# atmega32u4-tqfp44-breakout.net
KiCad netlist of a schematic drawn in EAGLE
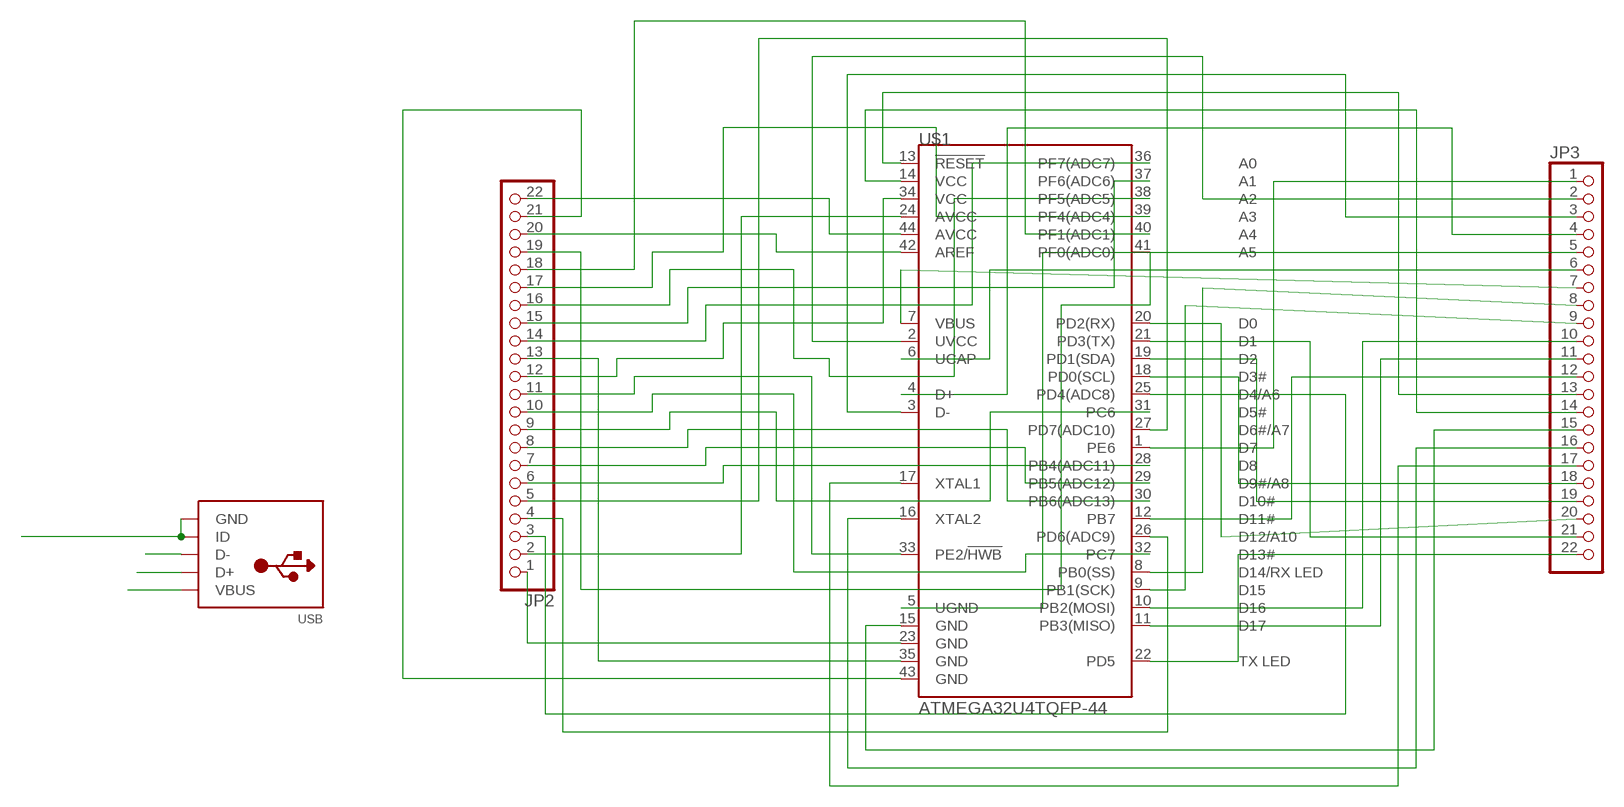
[diagram p0: schematic, sheet 1]

(export (version "E")
  (design (tool "Eeschema 10.0.6"))
  (components
    (comp (ref "JP2")
      (value "PINHD-1X22")
      (footprint "eagle-import:1X22")
      (libsource (lib "eagle-import") (part "PINHD-1X22"))
    )
    (comp (ref "JP3")
      (value "PINHD-1X22")
      (footprint "eagle-import:1X22")
      (libsource (lib "eagle-import") (part "PINHD-1X22"))
    )
    (comp (ref "U$1")
      (value "ATMEGA32U4TQFP-44")
      (footprint "eagle-import:TQFP44")
      (libsource (lib "eagle-import") (part "ATMEGA32U4TQFP-44"))
    )
    (comp (ref "USB")
      (value "USBMOLEX")
      (footprint "eagle-import:USB-MINIB-THM-MOLEX")
      (libsource (lib "eagle-import") (part "USBMOLEX"))
    )
  )
  (nets
    (net (code "1") (name "/N$21") (class "Default")
      (node (ref "JP3") (pin "22") (pinfunction "22_22") (pintype "passive"))
      (node (ref "U$1") (pin "22") (pinfunction "PD5_22") (pintype "bidirectional"))
      (node (ref "USB") (pin "D-") (pinfunction "D-_D-") (pintype "bidirectional"))
    )
    (net (code "2") (name "/N$23") (class "Default")
      (node (ref "JP2") (pin "1") (pinfunction "1_1") (pintype "passive"))
      (node (ref "U$1") (pin "23") (pinfunction "GND_23") (pintype "bidirectional"))
      (node (ref "USB") (pin "D+") (pinfunction "D+_D+") (pintype "bidirectional"))
    )
    (net (code "3") (name "Net-(JP2-Pad2)") (class "Default")
      (node (ref "JP2") (pin "2") (pinfunction "2_2") (pintype "passive"))
      (node (ref "U$1") (pin "24") (pinfunction "AVCC_24") (pintype "bidirectional"))
    )
    (net (code "4") (name "Net-(JP2-Pad12)") (class "Default")
      (node (ref "JP2") (pin "12") (pinfunction "12_12") (pintype "passive"))
      (node (ref "U$1") (pin "34") (pinfunction "VCC_34") (pintype "bidirectional"))
    )
    (net (code "5") (name "Net-(JP2-Pad13)") (class "Default")
      (node (ref "JP2") (pin "13") (pinfunction "13_13") (pintype "passive"))
      (node (ref "U$1") (pin "35") (pinfunction "GND_35") (pintype "bidirectional"))
    )
    (net (code "6") (name "Net-(JP2-Pad21)") (class "Default")
      (node (ref "JP2") (pin "21") (pinfunction "21_21") (pintype "passive"))
      (node (ref "U$1") (pin "43") (pinfunction "GND_43") (pintype "bidirectional"))
    )
    (net (code "7") (name "Net-(JP2-Pad22)") (class "Default")
      (node (ref "JP2") (pin "22") (pinfunction "22_22") (pintype "passive"))
      (node (ref "U$1") (pin "44") (pinfunction "AVCC_44") (pintype "bidirectional"))
    )
    (net (code "8") (name "Net-(JP3-Pad14)") (class "Default")
      (node (ref "JP3") (pin "14") (pinfunction "14_14") (pintype "passive"))
      (node (ref "U$1") (pin "14") (pinfunction "VCC_14") (pintype "bidirectional"))
    )
    (net (code "9") (name "Net-(JP3-Pad15)") (class "Default")
      (node (ref "JP3") (pin "15") (pinfunction "15_15") (pintype "passive"))
      (node (ref "U$1") (pin "15") (pinfunction "GND_15") (pintype "bidirectional"))
    )
    (net (code "10") (name "Net-(U$1-AREF)") (class "Default")
      (node (ref "JP2") (pin "20") (pinfunction "20_20") (pintype "passive"))
      (node (ref "U$1") (pin "42") (pinfunction "AREF_42") (pintype "bidirectional"))
    )
    (net (code "11") (name "Net-(U$1-D+)") (class "Default")
      (node (ref "JP3") (pin "4") (pinfunction "4_4") (pintype "passive"))
      (node (ref "U$1") (pin "4") (pinfunction "D+_4") (pintype "bidirectional"))
    )
    (net (code "12") (name "Net-(U$1-D-)") (class "Default")
      (node (ref "JP3") (pin "3") (pinfunction "3_3") (pintype "passive"))
      (node (ref "U$1") (pin "3") (pinfunction "D-_3") (pintype "bidirectional"))
    )
    (net (code "13") (name "Net-(U$1-PB0(SS))") (class "Default")
      (node (ref "JP3") (pin "8") (pinfunction "8_8") (pintype "passive"))
      (node (ref "U$1") (pin "8") (pinfunction "PB0(SS)_8") (pintype "bidirectional"))
    )
    (net (code "14") (name "Net-(U$1-PB1(SCK))") (class "Default")
      (node (ref "JP3") (pin "9") (pinfunction "9_9") (pintype "passive"))
      (node (ref "U$1") (pin "9") (pinfunction "PB1(SCK)_9") (pintype "bidirectional"))
    )
    (net (code "15") (name "Net-(U$1-PB2(MOSI))") (class "Default")
      (node (ref "JP3") (pin "10") (pinfunction "10_10") (pintype "passive"))
      (node (ref "U$1") (pin "10") (pinfunction "PB2(MOSI)_10") (pintype "bidirectional"))
    )
    (net (code "16") (name "Net-(U$1-PB3(MISO))") (class "Default")
      (node (ref "JP3") (pin "11") (pinfunction "11_11") (pintype "passive"))
      (node (ref "U$1") (pin "11") (pinfunction "PB3(MISO)_11") (pintype "bidirectional"))
    )
    (net (code "17") (name "Net-(U$1-PB4(ADC11))") (class "Default")
      (node (ref "JP2") (pin "6") (pinfunction "6_6") (pintype "passive"))
      (node (ref "U$1") (pin "28") (pinfunction "PB4(ADC11)_28") (pintype "bidirectional"))
    )
    (net (code "18") (name "Net-(U$1-PB5(ADC12))") (class "Default")
      (node (ref "JP2") (pin "7") (pinfunction "7_7") (pintype "passive"))
      (node (ref "U$1") (pin "29") (pinfunction "PB5(ADC12)_29") (pintype "bidirectional"))
    )
    (net (code "19") (name "Net-(U$1-PB6(ADC13))") (class "Default")
      (node (ref "JP2") (pin "8") (pinfunction "8_8") (pintype "passive"))
      (node (ref "U$1") (pin "30") (pinfunction "PB6(ADC13)_30") (pintype "bidirectional"))
    )
    (net (code "20") (name "Net-(U$1-PB7)") (class "Default")
      (node (ref "JP3") (pin "12") (pinfunction "12_12") (pintype "passive"))
      (node (ref "U$1") (pin "12") (pinfunction "PB7_12") (pintype "bidirectional"))
    )
    (net (code "21") (name "Net-(U$1-PC6)") (class "Default")
      (node (ref "JP2") (pin "9") (pinfunction "9_9") (pintype "passive"))
      (node (ref "U$1") (pin "31") (pinfunction "PC6_31") (pintype "bidirectional"))
    )
    (net (code "22") (name "Net-(U$1-PC7)") (class "Default")
      (node (ref "JP2") (pin "10") (pinfunction "10_10") (pintype "passive"))
      (node (ref "U$1") (pin "32") (pinfunction "PC7_32") (pintype "bidirectional"))
    )
    (net (code "23") (name "Net-(U$1-PD0(SCL))") (class "Default")
      (node (ref "JP3") (pin "18") (pinfunction "18_18") (pintype "passive"))
      (node (ref "U$1") (pin "18") (pinfunction "PD0(SCL)_18") (pintype "bidirectional"))
    )
    (net (code "24") (name "Net-(U$1-PD1(SDA))") (class "Default")
      (node (ref "JP3") (pin "19") (pinfunction "19_19") (pintype "passive"))
      (node (ref "U$1") (pin "19") (pinfunction "PD1(SDA)_19") (pintype "bidirectional"))
    )
    (net (code "25") (name "Net-(U$1-PD2(RX))") (class "Default")
      (node (ref "JP3") (pin "20") (pinfunction "20_20") (pintype "passive"))
      (node (ref "U$1") (pin "20") (pinfunction "PD2(RX)_20") (pintype "bidirectional"))
    )
    (net (code "26") (name "Net-(U$1-PD3(TX))") (class "Default")
      (node (ref "JP3") (pin "21") (pinfunction "21_21") (pintype "passive"))
      (node (ref "U$1") (pin "21") (pinfunction "PD3(TX)_21") (pintype "bidirectional"))
    )
    (net (code "27") (name "Net-(U$1-PD4(ADC8))") (class "Default")
      (node (ref "JP2") (pin "3") (pinfunction "3_3") (pintype "passive"))
      (node (ref "U$1") (pin "25") (pinfunction "PD4(ADC8)_25") (pintype "bidirectional"))
    )
    (net (code "28") (name "Net-(U$1-PD6(ADC9))") (class "Default")
      (node (ref "JP2") (pin "4") (pinfunction "4_4") (pintype "passive"))
      (node (ref "U$1") (pin "26") (pinfunction "PD6(ADC9)_26") (pintype "bidirectional"))
    )
    (net (code "29") (name "Net-(U$1-PD7(ADC10))") (class "Default")
      (node (ref "JP2") (pin "5") (pinfunction "5_5") (pintype "passive"))
      (node (ref "U$1") (pin "27") (pinfunction "PD7(ADC10)_27") (pintype "bidirectional"))
    )
    (net (code "30") (name "Net-(U$1-PE2{slash}~{HWB})") (class "Default")
      (node (ref "JP2") (pin "11") (pinfunction "11_11") (pintype "passive"))
      (node (ref "U$1") (pin "33") (pinfunction "PE2/~{HWB}_33") (pintype "bidirectional"))
    )
    (net (code "31") (name "Net-(U$1-PE6)") (class "Default")
      (node (ref "JP3") (pin "1") (pinfunction "1_1") (pintype "passive"))
      (node (ref "U$1") (pin "1") (pinfunction "PE6_1") (pintype "bidirectional"))
    )
    (net (code "32") (name "Net-(U$1-PF0(ADC0))") (class "Default")
      (node (ref "JP2") (pin "19") (pinfunction "19_19") (pintype "passive"))
      (node (ref "U$1") (pin "41") (pinfunction "PF0(ADC0)_41") (pintype "bidirectional"))
    )
    (net (code "33") (name "Net-(U$1-PF1(ADC1))") (class "Default")
      (node (ref "JP2") (pin "18") (pinfunction "18_18") (pintype "passive"))
      (node (ref "U$1") (pin "40") (pinfunction "PF1(ADC1)_40") (pintype "bidirectional"))
    )
    (net (code "34") (name "Net-(U$1-PF4(ADC4))") (class "Default")
      (node (ref "JP2") (pin "17") (pinfunction "17_17") (pintype "passive"))
      (node (ref "U$1") (pin "39") (pinfunction "PF4(ADC4)_39") (pintype "bidirectional"))
    )
    (net (code "35") (name "Net-(U$1-PF5(ADC5))") (class "Default")
      (node (ref "JP2") (pin "16") (pinfunction "16_16") (pintype "passive"))
      (node (ref "U$1") (pin "38") (pinfunction "PF5(ADC5)_38") (pintype "bidirectional"))
    )
    (net (code "36") (name "Net-(U$1-PF6(ADC6))") (class "Default")
      (node (ref "JP2") (pin "15") (pinfunction "15_15") (pintype "passive"))
      (node (ref "U$1") (pin "37") (pinfunction "PF6(ADC6)_37") (pintype "bidirectional"))
    )
    (net (code "37") (name "Net-(U$1-PF7(ADC7))") (class "Default")
      (node (ref "JP2") (pin "14") (pinfunction "14_14") (pintype "passive"))
      (node (ref "U$1") (pin "36") (pinfunction "PF7(ADC7)_36") (pintype "bidirectional"))
    )
    (net (code "38") (name "Net-(U$1-UCAP)") (class "Default")
      (node (ref "JP3") (pin "6") (pinfunction "6_6") (pintype "passive"))
      (node (ref "U$1") (pin "6") (pinfunction "UCAP_6") (pintype "bidirectional"))
    )
    (net (code "39") (name "Net-(U$1-UGND)") (class "Default")
      (node (ref "JP3") (pin "5") (pinfunction "5_5") (pintype "passive"))
      (node (ref "U$1") (pin "5") (pinfunction "UGND_5") (pintype "bidirectional"))
    )
    (net (code "40") (name "Net-(U$1-UVCC)") (class "Default")
      (node (ref "JP3") (pin "2") (pinfunction "2_2") (pintype "passive"))
      (node (ref "U$1") (pin "2") (pinfunction "UVCC_2") (pintype "bidirectional"))
    )
    (net (code "41") (name "Net-(U$1-VBUS)") (class "Default")
      (node (ref "JP3") (pin "7") (pinfunction "7_7") (pintype "passive"))
      (node (ref "U$1") (pin "7") (pinfunction "VBUS_7") (pintype "bidirectional"))
    )
    (net (code "42") (name "Net-(U$1-XTAL1)") (class "Default")
      (node (ref "JP3") (pin "17") (pinfunction "17_17") (pintype "passive"))
      (node (ref "U$1") (pin "17") (pinfunction "XTAL1_17") (pintype "bidirectional"))
    )
    (net (code "43") (name "Net-(U$1-XTAL2)") (class "Default")
      (node (ref "JP3") (pin "16") (pinfunction "16_16") (pintype "passive"))
      (node (ref "U$1") (pin "16") (pinfunction "XTAL2_16") (pintype "bidirectional"))
    )
    (net (code "44") (name "Net-(U$1-~{RESET})") (class "Default")
      (node (ref "JP3") (pin "13") (pinfunction "13_13") (pintype "passive"))
      (node (ref "U$1") (pin "13") (pinfunction "~{RESET}_13") (pintype "bidirectional"))
    )
    (net (code "45") (name "Net-(USB-PadGND)") (class "Default")
      (node (ref "USB") (pin "GND") (pinfunction "GND_GND") (pintype "power_in"))
      (node (ref "USB") (pin "ID") (pinfunction "ID_ID") (pintype "bidirectional"))
    )
    (net (code "46") (name "unconnected-(USB-PadVBUS)") (class "Default")
      (node (ref "USB") (pin "VBUS") (pinfunction "VBUS_VBUS") (pintype "power_in"))
    )
  )
)
